# NP_aktivni_standard_Sallen_Key.net
KiCad netlist of a schematic drawn in Altium Designer
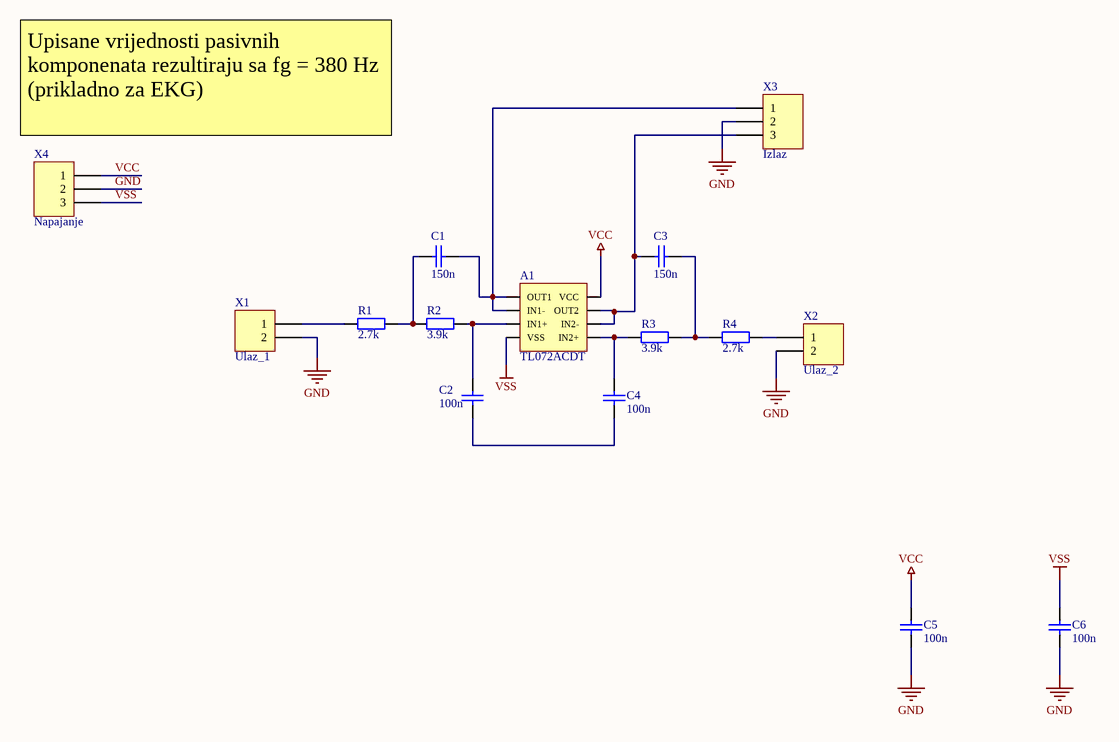
[diagram p0: NP_aktivni_standard_Sallen_Key.SchDoc]

(export (version "E")
  (design (tool "Eeschema 10.0.6"))
  (components
    (comp (ref "A1")
      (value "TL072ACDT")
      (footprint "ADI-R-8_N")
      (description "Dual opamp")
      (libsource (lib "Schlib1") (part "TL072ACDT"))
    )
    (comp (ref "C1")
      (value "150n")
      (footprint "J1-0603")
      (description "Capacitor")
      (fields (field (name "PUBLISHER") "Altium Limited"))
      (libsource (lib "Miscellaneous Devices") (part "Cap"))
    )
    (comp (ref "C2")
      (value "100n")
      (footprint "J1-0603")
      (description "Capacitor")
      (fields (field (name "PUBLISHER") "Altium Limited"))
      (libsource (lib "Miscellaneous Devices") (part "Cap"))
    )
    (comp (ref "C3")
      (value "150n")
      (footprint "J1-0603")
      (description "Capacitor")
      (fields (field (name "PUBLISHER") "Altium Limited"))
      (libsource (lib "Miscellaneous Devices") (part "Cap"))
    )
    (comp (ref "C4")
      (value "100n")
      (footprint "J1-0603")
      (description "Capacitor")
      (fields (field (name "PUBLISHER") "Altium Limited"))
      (libsource (lib "Miscellaneous Devices") (part "Cap"))
    )
    (comp (ref "C5")
      (value "100n")
      (footprint "J1-0603")
      (description "Capacitor")
      (fields (field (name "PUBLISHER") "Altium Limited"))
      (libsource (lib "Miscellaneous Devices") (part "Cap"))
    )
    (comp (ref "C6")
      (value "100n")
      (footprint "J1-0603")
      (description "Capacitor")
      (fields (field (name "PUBLISHER") "Altium Limited"))
      (libsource (lib "Miscellaneous Devices") (part "Cap"))
    )
    (comp (ref "R1")
      (value "2.7k")
      (footprint "J1-0603")
      (description "Resistor")
      (fields (field (name "PUBLISHER") "Altium Limited"))
      (libsource (lib "Miscellaneous Devices") (part "Res2"))
    )
    (comp (ref "R2")
      (value "3.9k")
      (footprint "J1-0603")
      (description "Resistor")
      (fields (field (name "PUBLISHER") "Altium Limited"))
      (libsource (lib "Miscellaneous Devices") (part "Res2"))
    )
    (comp (ref "R3")
      (value "3.9k")
      (footprint "J1-0603")
      (description "Resistor")
      (fields (field (name "PUBLISHER") "Altium Limited"))
      (libsource (lib "Miscellaneous Devices") (part "Res2"))
    )
    (comp (ref "R4")
      (value "2.7k")
      (footprint "J1-0603")
      (description "Resistor")
      (fields (field (name "PUBLISHER") "Altium Limited"))
      (libsource (lib "Miscellaneous Devices") (part "Res2"))
    )
    (comp (ref "X1")
      (value "Ulaz_1")
      (footprint "HDR1X2")
      (description "Header, 2-Pin")
      (fields (field (name "PUBLISHER") "Altium Limited"))
      (libsource (lib "Miscellaneous Connectors") (part "Header 2"))
    )
    (comp (ref "X2")
      (value "Ulaz_2")
      (footprint "HDR1X2")
      (description "Header, 2-Pin")
      (fields (field (name "PUBLISHER") "Altium Limited"))
      (libsource (lib "") (part "Header 2_1"))
    )
    (comp (ref "X3")
      (value "Izlaz")
      (footprint "HDR1X3")
      (description "Header, 3-Pin")
      (fields (field (name "PUBLISHER") "Altium Limited"))
      (libsource (lib "") (part "Header 3_1"))
    )
    (comp (ref "X4")
      (value "Napajanje")
      (footprint "HDR1X3")
      (description "Header, 3-Pin")
      (fields (field (name "PUBLISHER") "Altium Limited"))
      (libsource (lib "Miscellaneous Connectors") (part "Header 3"))
    )
  )
  (nets
    (net (code "1") (name "GND") (class "Default")
      (node (ref "C5") (pin "1") (pinfunction "1_1") (pintype "passive"))
      (node (ref "C6") (pin "1") (pinfunction "1_1") (pintype "passive"))
      (node (ref "X1") (pin "2") (pinfunction "2_2") (pintype "passive"))
      (node (ref "X2") (pin "2") (pinfunction "2_2") (pintype "passive"))
      (node (ref "X3") (pin "2") (pinfunction "2_2") (pintype "passive"))
      (node (ref "X4") (pin "2") (pinfunction "2_2") (pintype "passive"))
    )
    (net (code "2") (name "Net-(A1-IN1+)") (class "Default")
      (node (ref "A1") (pin "3") (pinfunction "IN1+_3") (pintype "passive"))
      (node (ref "C2") (pin "2") (pinfunction "2_2") (pintype "passive"))
      (node (ref "R2") (pin "2") (pinfunction "2_2") (pintype "passive"))
    )
    (net (code "3") (name "Net-(A1-IN1-)") (class "Default")
      (node (ref "A1") (pin "1") (pinfunction "OUT1_1") (pintype "passive"))
      (node (ref "A1") (pin "2") (pinfunction "IN1-_2") (pintype "passive"))
      (node (ref "C1") (pin "2") (pinfunction "2_2") (pintype "passive"))
      (node (ref "X3") (pin "1") (pinfunction "1_1") (pintype "passive"))
    )
    (net (code "4") (name "Net-(A1-IN2+)") (class "Default")
      (node (ref "A1") (pin "5") (pinfunction "IN2+_5") (pintype "passive"))
      (node (ref "C4") (pin "1") (pinfunction "1_1") (pintype "passive"))
      (node (ref "R3") (pin "1") (pinfunction "1_1") (pintype "passive"))
    )
    (net (code "5") (name "Net-(A1-IN2-)") (class "Default")
      (node (ref "A1") (pin "6") (pinfunction "IN2-_6") (pintype "passive"))
      (node (ref "A1") (pin "7") (pinfunction "OUT2_7") (pintype "passive"))
      (node (ref "C3") (pin "2") (pinfunction "2_2") (pintype "passive"))
      (node (ref "X3") (pin "3") (pinfunction "3_3") (pintype "passive"))
    )
    (net (code "6") (name "Net-(C1-Pad1)") (class "Default")
      (node (ref "C1") (pin "1") (pinfunction "1_1") (pintype "passive"))
      (node (ref "R1") (pin "2") (pinfunction "2_2") (pintype "passive"))
      (node (ref "R2") (pin "1") (pinfunction "1_1") (pintype "passive"))
    )
    (net (code "7") (name "Net-(C2-Pad1)") (class "Default")
      (node (ref "C2") (pin "1") (pinfunction "1_1") (pintype "passive"))
      (node (ref "C4") (pin "2") (pinfunction "2_2") (pintype "passive"))
    )
    (net (code "8") (name "Net-(C3-Pad1)") (class "Default")
      (node (ref "C3") (pin "1") (pinfunction "1_1") (pintype "passive"))
      (node (ref "R3") (pin "2") (pinfunction "2_2") (pintype "passive"))
      (node (ref "R4") (pin "1") (pinfunction "1_1") (pintype "passive"))
    )
    (net (code "9") (name "Net-(R1-Pad1)") (class "Default")
      (node (ref "R1") (pin "1") (pinfunction "1_1") (pintype "passive"))
      (node (ref "X1") (pin "1") (pinfunction "1_1") (pintype "passive"))
    )
    (net (code "10") (name "Net-(R4-Pad2)") (class "Default")
      (node (ref "R4") (pin "2") (pinfunction "2_2") (pintype "passive"))
      (node (ref "X2") (pin "1") (pinfunction "1_1") (pintype "passive"))
    )
    (net (code "11") (name "VCC") (class "Default")
      (node (ref "A1") (pin "8") (pinfunction "VCC_8") (pintype "passive"))
      (node (ref "C5") (pin "2") (pinfunction "2_2") (pintype "passive"))
      (node (ref "X4") (pin "1") (pinfunction "1_1") (pintype "passive"))
    )
    (net (code "12") (name "VSS") (class "Default")
      (node (ref "A1") (pin "4") (pinfunction "VSS_4") (pintype "passive"))
      (node (ref "C6") (pin "2") (pinfunction "2_2") (pintype "passive"))
      (node (ref "X4") (pin "3") (pinfunction "3_3") (pintype "passive"))
    )
  )
)
